# Qbot.net
KiCad netlist of a schematic drawn in Altium Designer
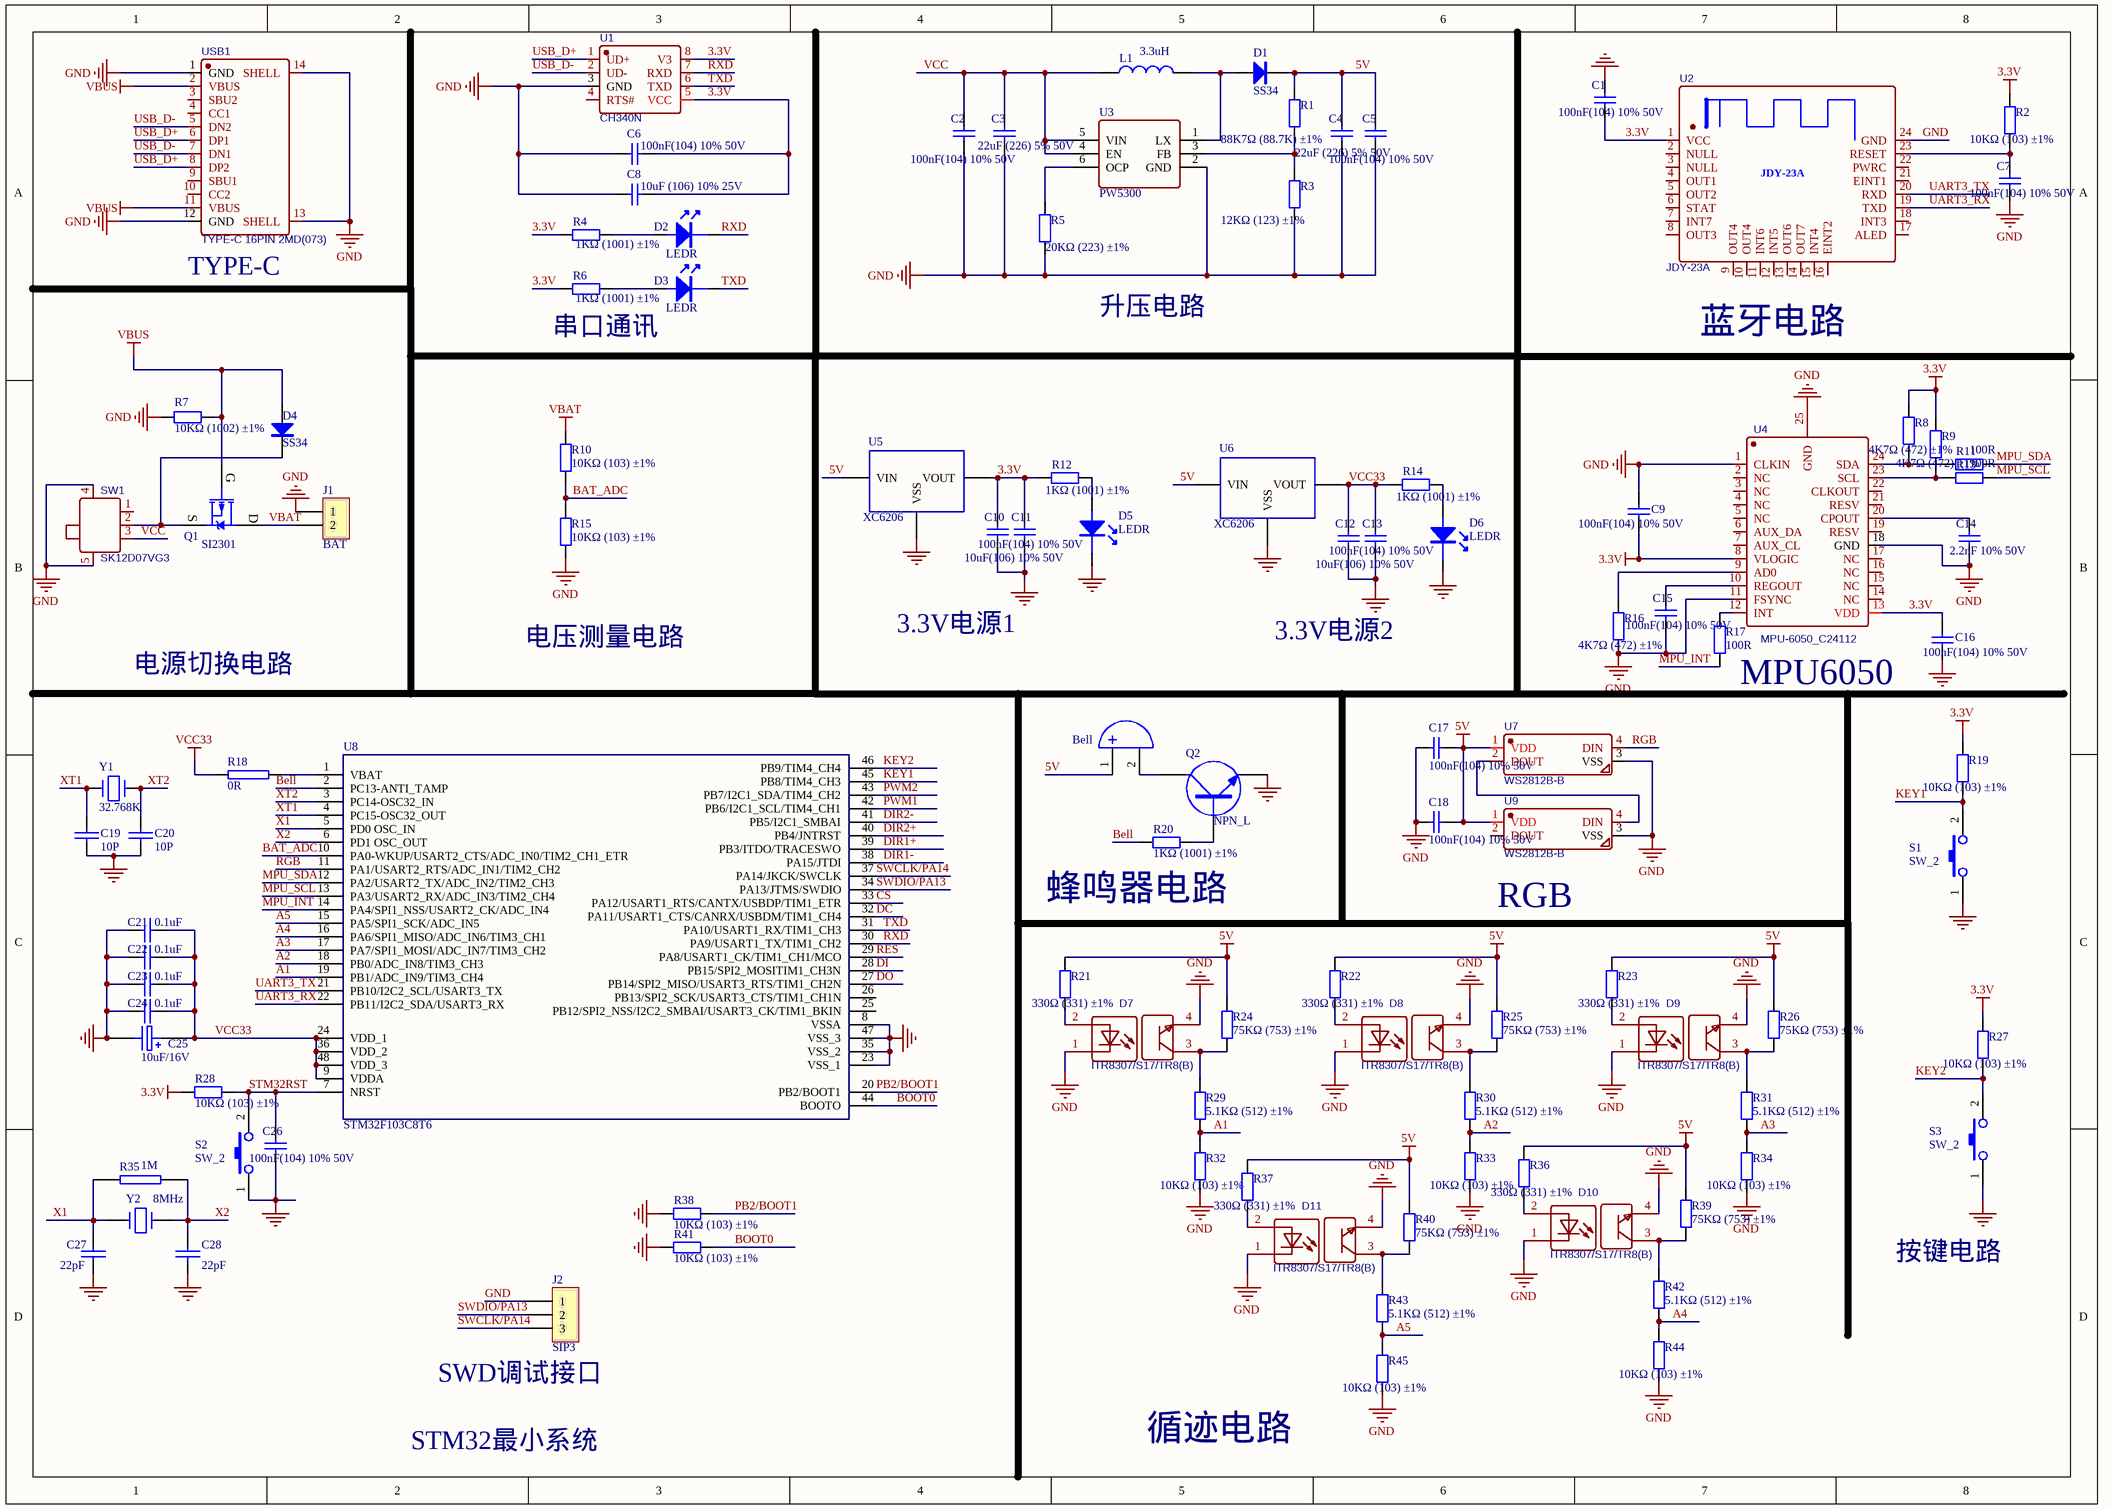
[diagram p0: Qbot.SchDoc]

(export (version "E")
  (design (tool "Eeschema 10.0.6"))
  (components
    (comp (ref "C1")
      (value "100nF(104) 10% 50V")
      (footprint "LC-0805_C")
      (description "贴片电容")
      (libsource (lib "Miscellaneous Devices LC") (part "0805 100nF(104) 10% 50V"))
    )
    (comp (ref "C2")
      (value "100nF(104) 10% 50V")
      (footprint "LC-0805_C")
      (description "贴片电容")
      (libsource (lib "Miscellaneous Devices LC") (part "0805 100nF(104) 10% 50V"))
    )
    (comp (ref "C3")
      (value "22uF (226) 5% 50V")
      (footprint "LC-0805_C")
      (description "贴片电容")
      (libsource (lib "Miscellaneous Devices LC") (part "0805 22pF (220) 5% 50V"))
    )
    (comp (ref "C4")
      (value "22uF (226) 5% 50V")
      (footprint "LC-0805_C")
      (description "贴片电容")
      (libsource (lib "Miscellaneous Devices LC") (part "0805 22pF (220) 5% 50V"))
    )
    (comp (ref "C5")
      (value "100nF(104) 10% 50V")
      (footprint "LC-0805_C")
      (description "贴片电容")
      (libsource (lib "Miscellaneous Devices LC") (part "0805 100nF(104) 10% 50V"))
    )
    (comp (ref "C6")
      (value "100nF(104) 10% 50V")
      (footprint "LC-0805_C")
      (description "贴片电容")
      (libsource (lib "Miscellaneous Devices LC") (part "0805 100nF(104) 10% 50V"))
    )
    (comp (ref "C7")
      (value "100nF(104) 10% 50V")
      (footprint "LC-0805_C")
      (description "贴片电容")
      (libsource (lib "Miscellaneous Devices LC") (part "0805 100nF(104) 10% 50V"))
    )
    (comp (ref "C8")
      (value "10uF (106) 10% 25V")
      (footprint "LC-0805_C")
      (description "贴片电容")
      (libsource (lib "Miscellaneous Devices LC") (part "0805 10uF (106) 10% 25V"))
    )
    (comp (ref "C9")
      (value "100nF(104) 10% 50V")
      (footprint "LC-0805_C")
      (description "贴片电容")
      (libsource (lib "Miscellaneous Devices LC") (part "0805 100nF(104) 10% 50V"))
    )
    (comp (ref "C10")
      (value "10uF(106) 10% 50V")
      (footprint "LC-0805_C")
      (description "贴片电容")
      (libsource (lib "Miscellaneous Devices LC") (part "0805 100nF(104) 10% 50V"))
    )
    (comp (ref "C11")
      (value "100nF(104) 10% 50V")
      (footprint "LC-0805_C")
      (description "贴片电容")
      (libsource (lib "Miscellaneous Devices LC") (part "0805 100nF(104) 10% 50V"))
    )
    (comp (ref "C12")
      (value "10uF(106) 10% 50V")
      (footprint "LC-0805_C")
      (description "贴片电容")
      (libsource (lib "Miscellaneous Devices LC") (part "0805 100nF(104) 10% 50V"))
    )
    (comp (ref "C13")
      (value "100nF(104) 10% 50V")
      (footprint "LC-0805_C")
      (description "贴片电容")
      (libsource (lib "Miscellaneous Devices LC") (part "0805 100nF(104) 10% 50V"))
    )
    (comp (ref "C14")
      (value "2.2nF 10% 50V")
      (footprint "LC-0805_C")
      (description "贴片电容")
      (libsource (lib "Miscellaneous Devices LC") (part "0805 100nF(104) 10% 50V"))
    )
    (comp (ref "C15")
      (value "100nF(104) 10% 50V")
      (footprint "LC-0805_C")
      (description "贴片电容")
      (libsource (lib "Miscellaneous Devices LC") (part "0805 100nF(104) 10% 50V"))
    )
    (comp (ref "C16")
      (value "100nF(104) 10% 50V")
      (footprint "LC-0805_C")
      (description "贴片电容")
      (libsource (lib "Miscellaneous Devices LC") (part "0805 100nF(104) 10% 50V"))
    )
    (comp (ref "C17")
      (value "100nF(104) 10% 50V")
      (footprint "LC-0805_C")
      (description "贴片电容")
      (libsource (lib "Miscellaneous Devices LC") (part "0805 100nF(104) 10% 50V"))
    )
    (comp (ref "C18")
      (value "100nF(104) 10% 50V")
      (footprint "LC-0805_C")
      (description "贴片电容")
      (libsource (lib "Miscellaneous Devices LC") (part "0805 100nF(104) 10% 50V"))
    )
    (comp (ref "C19") (value "10P") (footprint "LC-0805_C") (libsource (lib "*") (part "CAP")))
    (comp (ref "C20") (value "10P") (footprint "LC-0805_C") (libsource (lib "*") (part "CAP")))
    (comp (ref "C21")
      (value "0.1uF")
      (footprint "LC-0805_C")
      (description "Capacitor")
      (libsource (lib "") (part "CAP_1"))
    )
    (comp (ref "C22")
      (value "0.1uF")
      (footprint "LC-0805_C")
      (description "Capacitor")
      (libsource (lib "") (part "CAP_1"))
    )
    (comp (ref "C23")
      (value "0.1uF")
      (footprint "LC-0805_C")
      (description "Capacitor")
      (libsource (lib "") (part "CAP_1"))
    )
    (comp (ref "C24")
      (value "0.1uF")
      (footprint "LC-0805_C")
      (description "Capacitor")
      (libsource (lib "") (part "CAP_1"))
    )
    (comp (ref "C25")
      (value "10uF/16V")
      (footprint "LC-0805_C")
      (description "Electrolytic Capacitor")
      (libsource (lib "*") (part "ELECTRO1"))
    )
    (comp (ref "C26")
      (value "100nF(104) 10% 50V")
      (footprint "LC-0805_C")
      (description "贴片电容")
      (libsource (lib "Miscellaneous Devices LC") (part "0805 100nF(104) 10% 50V"))
    )
    (comp (ref "C27")
      (value "22pF")
      (footprint "LC-0805_C")
      (description "Capacitor")
      (libsource (lib "") (part "CAP_1"))
    )
    (comp (ref "C28")
      (value "22pF")
      (footprint "LC-0805_C")
      (description "Capacitor")
      (libsource (lib "") (part "CAP_1"))
    )
    (comp (ref "D1")
      (value "SS34")
      (footprint "SMA")
      (description "肖特基二极管")
      (fields (field (name "版权归属") "源创客"))
      (libsource (lib "8.1   - 二极管-整流桥") (part "SS34"))
    )
    (comp (ref "D2") (value "LEDR") (footprint "LED0805G") (libsource (lib "六路AD&六路DA_1") (part "LED")))
    (comp (ref "D3") (value "LEDR") (footprint "LED0805G") (libsource (lib "六路AD&六路DA_1") (part "LED")))
    (comp (ref "D4")
      (value "SS34")
      (footprint "SMA")
      (description "肖特基二极管")
      (fields (field (name "版权归属") "源创客"))
      (libsource (lib "8.1   - 二极管-整流桥") (part "SS34"))
    )
    (comp (ref "D5") (value "LEDR") (footprint "LED0805G") (libsource (lib "*") (part "LED")))
    (comp (ref "D6") (value "LEDR") (footprint "LED0805G") (libsource (lib "*") (part "LED")))
    (comp (ref "D7")
      (value "ITR8307/S17/TR8(B)")
      (footprint "OPTO-SMD_ITR8307-S17-TR8-B-BL")
      (fields (field (name "BOM_SUPPLIER PART") "C81632"))
      (libsource (lib "Qbot") (part "ITR8307/S17/TR8(B)"))
    )
    (comp (ref "D8")
      (value "ITR8307/S17/TR8(B)")
      (footprint "OPTO-SMD_ITR8307-S17-TR8-B-BL")
      (fields (field (name "BOM_SUPPLIER PART") "C81632"))
      (libsource (lib "Qbot") (part "ITR8307/S17/TR8(B)"))
    )
    (comp (ref "D9")
      (value "ITR8307/S17/TR8(B)")
      (footprint "OPTO-SMD_ITR8307-S17-TR8-B-BL")
      (fields (field (name "BOM_SUPPLIER PART") "C81632"))
      (libsource (lib "Qbot") (part "ITR8307/S17/TR8(B)"))
    )
    (comp (ref "D10")
      (value "ITR8307/S17/TR8(B)")
      (footprint "OPTO-SMD_ITR8307-S17-TR8-B-BL")
      (fields (field (name "BOM_SUPPLIER PART") "C81632"))
      (libsource (lib "Qbot") (part "ITR8307/S17/TR8(B)"))
    )
    (comp (ref "D11")
      (value "ITR8307/S17/TR8(B)")
      (footprint "OPTO-SMD_ITR8307-S17-TR8-B-BL")
      (fields (field (name "BOM_SUPPLIER PART") "C81632"))
      (libsource (lib "Qbot") (part "ITR8307/S17/TR8(B)"))
    )
    (comp (ref "J1")
      (value "BAT")
      (footprint "XH2.54-LI-2P")
      (description "jointbar")
      (libsource (lib "接口与插座") (part "SIP2"))
    )
    (comp (ref "J2")
      (value "SIP3")
      (footprint "HDR2.54-WI-3P")
      (description "jointbar")
      (libsource (lib "接口与插座") (part "SIP3"))
    )
    (comp (ref "L1")
      (value "3.3uH")
      (footprint "IND-SMD_L4.6-W4.1")
      (description "小功率贴片电感")
      (fields (field (name "版权归属") "源创客"))
      (libsource (lib "3.1   - 电阻-电容-电感") (part "L"))
    )
    (comp (ref "LS1")
      (value "Bell")
      (footprint "BELL")
      (description "Electrical Bell")
      (fields (field (name "PUBLISHER") "Altium Limited"))
      (libsource (lib "3DGeneral") (part "Bell"))
    )
    (comp (ref "Q1")
      (value "SI2301")
      (footprint "SOT23")
      (description "P沟道场效应管")
      (fields (field (name "版权归属") "源创客"))
      (libsource (lib "6.1   - 场效应管-可控硅") (part "SI2301"))
    )
    (comp (ref "Q2")
      (value "NPN_L")
      (footprint "SOT-23_S8050")
      (libsource (lib "Environment_Detector") (part "NPN_L"))
    )
    (comp (ref "R1")
      (value "88K7Ω (88.7K) ±1%")
      (footprint "LC-0805_R")
      (description "贴片电阻")
      (libsource (lib "Miscellaneous Devices LC") (part "0805 1KΩ (1001) 1%"))
    )
    (comp (ref "R2")
      (value "10KΩ (103) ±1%")
      (footprint "LC-0805_R")
      (description "贴片电阻")
      (libsource (lib "") (part "0805 1KΩ (1001) 1%_2"))
    )
    (comp (ref "R3")
      (value "12KΩ (123) ±1%")
      (footprint "LC-0805_R")
      (description "贴片电阻")
      (libsource (lib "Miscellaneous Devices LC") (part "0805 1KΩ (1001) 1%"))
    )
    (comp (ref "R4")
      (value "1KΩ (1001) ±1%")
      (footprint "LC-0805_R")
      (description "贴片电阻")
      (libsource (lib "") (part "0805 1KΩ (1001) 1%_1"))
    )
    (comp (ref "R5")
      (value "20KΩ (223) ±1%")
      (footprint "LC-0805_R")
      (description "贴片电阻")
      (libsource (lib "Miscellaneous Devices LC") (part "0805 1KΩ (1001) 1%"))
    )
    (comp (ref "R6")
      (value "1KΩ (1001) ±1%")
      (footprint "LC-0805_R")
      (description "贴片电阻")
      (libsource (lib "") (part "0805 1KΩ (1001) 1%_1"))
    )
    (comp (ref "R7")
      (value "10KΩ (1002) ±1%")
      (footprint "LC-0805_R")
      (description "贴片电阻")
      (libsource (lib "Miscellaneous Devices LC") (part "0805 10KΩ (1002) 1%"))
    )
    (comp (ref "R8")
      (value "4K7Ω (472) ±1%")
      (footprint "LC-0805_R")
      (description "贴片电阻")
      (libsource (lib "") (part "0805 1KΩ (1001) 1%_2"))
    )
    (comp (ref "R9")
      (value "4K7Ω (472) ±1%")
      (footprint "LC-0805_R")
      (description "贴片电阻")
      (libsource (lib "") (part "0805 1KΩ (1001) 1%_2"))
    )
    (comp (ref "R10")
      (value "10KΩ (103) ±1%")
      (footprint "LC-0805_R")
      (description "贴片电阻")
      (libsource (lib "") (part "0805 1KΩ (1001) 1%_2"))
    )
    (comp (ref "R11")
      (value "100R")
      (footprint "LC-0805_R")
      (description "贴片电阻")
      (libsource (lib "") (part "0805 1KΩ (1001) 1%_1"))
    )
    (comp (ref "R12")
      (value "1KΩ (1001) ±1%")
      (footprint "LC-0805_R")
      (description "贴片电阻")
      (libsource (lib "") (part "0805 1KΩ (1001) 1%_1"))
    )
    (comp (ref "R13")
      (value "100R")
      (footprint "LC-0805_R")
      (description "贴片电阻")
      (libsource (lib "") (part "0805 1KΩ (1001) 1%_1"))
    )
    (comp (ref "R14")
      (value "1KΩ (1001) ±1%")
      (footprint "LC-0805_R")
      (description "贴片电阻")
      (libsource (lib "") (part "0805 1KΩ (1001) 1%_1"))
    )
    (comp (ref "R15")
      (value "10KΩ (103) ±1%")
      (footprint "LC-0805_R")
      (description "贴片电阻")
      (libsource (lib "") (part "0805 1KΩ (1001) 1%_2"))
    )
    (comp (ref "R16")
      (value "4K7Ω (472) ±1%")
      (footprint "LC-0805_R")
      (description "贴片电阻")
      (libsource (lib "") (part "0805 1KΩ (1001) 1%_2"))
    )
    (comp (ref "R17")
      (value "100R")
      (footprint "LC-0805_R")
      (description "贴片电阻")
      (libsource (lib "Miscellaneous Devices LC") (part "0805 1KΩ (1001) 1%"))
    )
    (comp (ref "R18") (value "0R") (footprint "LC-0805_R") (libsource (lib "*") (part "RES")))
    (comp (ref "R19")
      (value "10KΩ (103) ±1%")
      (footprint "LC-0805_R")
      (description "贴片电阻")
      (libsource (lib "") (part "0805 1KΩ (1001) 1%_2"))
    )
    (comp (ref "R20")
      (value "1KΩ (1001) ±1%")
      (footprint "LC-0805_R")
      (description "贴片电阻")
      (libsource (lib "") (part "0805 1KΩ (1001) 1%_1"))
    )
    (comp (ref "R21")
      (value "330Ω (331) ±1%")
      (footprint "LC-0805_R")
      (description "贴片电阻")
      (libsource (lib "Miscellaneous Devices LC") (part "0805 1KΩ (1001) 1%"))
    )
    (comp (ref "R22")
      (value "330Ω (331) ±1%")
      (footprint "LC-0805_R")
      (description "贴片电阻")
      (libsource (lib "Miscellaneous Devices LC") (part "0805 1KΩ (1001) 1%"))
    )
    (comp (ref "R23")
      (value "330Ω (331) ±1%")
      (footprint "LC-0805_R")
      (description "贴片电阻")
      (libsource (lib "Miscellaneous Devices LC") (part "0805 1KΩ (1001) 1%"))
    )
    (comp (ref "R24")
      (value "75KΩ (753) ±1%")
      (footprint "LC-0805_R")
      (description "贴片电阻")
      (libsource (lib "") (part "0805 1KΩ (1001) 1%_2"))
    )
    (comp (ref "R25")
      (value "75KΩ (753) ±1%")
      (footprint "LC-0805_R")
      (description "贴片电阻")
      (libsource (lib "") (part "0805 1KΩ (1001) 1%_2"))
    )
    (comp (ref "R26")
      (value "75KΩ (753) ±1%")
      (footprint "LC-0805_R")
      (description "贴片电阻")
      (libsource (lib "") (part "0805 1KΩ (1001) 1%_2"))
    )
    (comp (ref "R27")
      (value "10KΩ (103) ±1%")
      (footprint "LC-0805_R")
      (description "贴片电阻")
      (libsource (lib "") (part "0805 1KΩ (1001) 1%_2"))
    )
    (comp (ref "R28")
      (value "10KΩ (103) ±1%")
      (footprint "LC-0805_R")
      (description "贴片电阻")
      (libsource (lib "") (part "0805 1KΩ (1001) 1%_3"))
    )
    (comp (ref "R29")
      (value "5.1KΩ (512) ±1%")
      (footprint "LC-0805_R")
      (description "贴片电阻")
      (libsource (lib "Miscellaneous Devices LC") (part "0805 1KΩ (1001) 1%"))
    )
    (comp (ref "R30")
      (value "5.1KΩ (512) ±1%")
      (footprint "LC-0805_R")
      (description "贴片电阻")
      (libsource (lib "Miscellaneous Devices LC") (part "0805 1KΩ (1001) 1%"))
    )
    (comp (ref "R31")
      (value "5.1KΩ (512) ±1%")
      (footprint "LC-0805_R")
      (description "贴片电阻")
      (libsource (lib "Miscellaneous Devices LC") (part "0805 1KΩ (1001) 1%"))
    )
    (comp (ref "R32")
      (value "10KΩ (103) ±1%")
      (footprint "LC-0805_R")
      (description "贴片电阻")
      (libsource (lib "") (part "0805 1KΩ (1001) 1%_2"))
    )
    (comp (ref "R33")
      (value "10KΩ (103) ±1%")
      (footprint "LC-0805_R")
      (description "贴片电阻")
      (libsource (lib "") (part "0805 1KΩ (1001) 1%_2"))
    )
    (comp (ref "R34")
      (value "10KΩ (103) ±1%")
      (footprint "LC-0805_R")
      (description "贴片电阻")
      (libsource (lib "") (part "0805 1KΩ (1001) 1%_2"))
    )
    (comp (ref "R35") (value "1M") (footprint "LC-0805_R") (libsource (lib "*") (part "RES2")))
    (comp (ref "R36")
      (value "330Ω (331) ±1%")
      (footprint "LC-0805_R")
      (description "贴片电阻")
      (libsource (lib "Miscellaneous Devices LC") (part "0805 1KΩ (1001) 1%"))
    )
    (comp (ref "R37")
      (value "330Ω (331) ±1%")
      (footprint "LC-0805_R")
      (description "贴片电阻")
      (libsource (lib "Miscellaneous Devices LC") (part "0805 1KΩ (1001) 1%"))
    )
    (comp (ref "R38")
      (value "10KΩ (103) ±1%")
      (footprint "LC-0805_R")
      (description "贴片电阻")
      (libsource (lib "") (part "0805 1KΩ (1001) 1%_1"))
    )
    (comp (ref "R39")
      (value "75KΩ (753) ±1%")
      (footprint "LC-0805_R")
      (description "贴片电阻")
      (libsource (lib "") (part "0805 1KΩ (1001) 1%_2"))
    )
    (comp (ref "R40")
      (value "75KΩ (753) ±1%")
      (footprint "LC-0805_R")
      (description "贴片电阻")
      (libsource (lib "") (part "0805 1KΩ (1001) 1%_2"))
    )
    (comp (ref "R41")
      (value "10KΩ (103) ±1%")
      (footprint "LC-0805_R")
      (description "贴片电阻")
      (libsource (lib "") (part "0805 1KΩ (1001) 1%_1"))
    )
    (comp (ref "R42")
      (value "5.1KΩ (512) ±1%")
      (footprint "LC-0805_R")
      (description "贴片电阻")
      (libsource (lib "Miscellaneous Devices LC") (part "0805 1KΩ (1001) 1%"))
    )
    (comp (ref "R43")
      (value "5.1KΩ (512) ±1%")
      (footprint "LC-0805_R")
      (description "贴片电阻")
      (libsource (lib "Miscellaneous Devices LC") (part "0805 1KΩ (1001) 1%"))
    )
    (comp (ref "R44")
      (value "10KΩ (103) ±1%")
      (footprint "LC-0805_R")
      (description "贴片电阻")
      (libsource (lib "") (part "0805 1KΩ (1001) 1%_2"))
    )
    (comp (ref "R45")
      (value "10KΩ (103) ±1%")
      (footprint "LC-0805_R")
      (description "贴片电阻")
      (libsource (lib "") (part "0805 1KΩ (1001) 1%_2"))
    )
    (comp (ref "S1") (value "SW_2") (footprint "TSW SMD-3*6*2.5") (libsource (lib "*") (part "SW_2")))
    (comp (ref "S2") (value "SW_2") (footprint "TSW SMD-3*6*2.5") (libsource (lib "*") (part "SW_2")))
    (comp (ref "S3") (value "SW_2") (footprint "TSW SMD-3*6*2.5") (libsource (lib "*") (part "SW_2")))
    (comp (ref "SW1")
      (value "SK12D07VG3")
      (footprint "SW-TH_SK-12D07-VG3")
      (fields
        (field (name "BOM_SUPPLIER PART") "C2681575")
        (field (name "BOM_MANUFACTURER PART") "SK12D07VG6")
        (field (name "CONTRIBUTOR") "LCSC")
      )
      (libsource (lib "Qbot") (part "SK12D07VG6"))
    )
    (comp (ref "U1")
      (value "CH340N")
      (footprint "SOP8")
      (fields
        (field (name "BOM_SUPPLIER PART") "C506813")
        (field (name "SUBPART_NO") "1")
        (field (name "CONTRIBUTOR") "LCSC")
      )
      (libsource (lib "Qbot") (part "CH340N"))
    )
    (comp (ref "U2")
      (value "JDY-23A")
      (footprint "JDY-23A")
      (fields
        (field (name "BOM_MANUFACTURER PART") "HY-40R204P")
        (field (name "BOM_SUPPLIER PART") "C172803")
        (field (name "CONTRIBUTOR") "LCSC")
      )
      (libsource (lib "Qbot") (part "JDY-23A"))
    )
    (comp (ref "U3") (value "PW5300") (footprint "SOT23-6L") (libsource (lib "Qbot") (part "PW5300")))
    (comp (ref "U4")
      (value "MPU-6050_C24112")
      (footprint "QFN24")
      (fields (field (name "BOM_MANUFACTURER PART") "MPU-6050") (field (name "BOM_SUPPLIER PART") "C24112"))
      (libsource (lib "Qbot") (part "MPU-6050_C24112"))
    )
    (comp (ref "U5") (value "XC6206") (footprint "SOT-23_TL431") (libsource (lib "*") (part "XC6206")))
    (comp (ref "U6") (value "XC6206") (footprint "SOT-23_TL431") (libsource (lib "*") (part "XC6206")))
    (comp (ref "U7")
      (value "WS2812B-B")
      (footprint "LED-SMD_4P-L5.0-W5.0-TL_WS2812B-B")
      (fields (field (name "BOM_SUPPLIER PART") "C114586") (field (name "CONTRIBUTOR") "LCSC"))
      (libsource (lib "Qbot") (part "WS2812B-B"))
    )
    (comp (ref "U8")
      (value "STM32F103C8T6")
      (footprint "STM32F103C8T6_LQFP48")
      (libsource (lib "*") (part "STM32F103C8T6"))
    )
    (comp (ref "U9")
      (value "WS2812B-B")
      (footprint "LED-SMD_4P-L5.0-W5.0-TL_WS2812B-B")
      (fields (field (name "BOM_SUPPLIER PART") "C114586") (field (name "CONTRIBUTOR") "LCSC"))
      (libsource (lib "Qbot") (part "WS2812B-B"))
    )
    (comp (ref "USB1")
      (value "TYPE-C 16PIN 2MD(073)")
      (footprint "USB-C-SMD_TYPE-C-6PIN-2MD-073")
      (fields (field (name "BOM_SUPPLIER PART") "C2765186") (field (name "CONTRIBUTOR") "LCSC"))
      (libsource (lib "Qbot") (part "TYPE-C 16PIN 2MD(073)"))
    )
    (comp (ref "Y1")
      (value "32.768K")
      (footprint "OSC-3x10-WI-A")
      (description "晶振")
      (libsource (lib "*") (part "CRYSTAL"))
    )
    (comp (ref "Y2")
      (value "8MHz")
      (footprint "OSC HC-49S")
      (description "Crystal")
      (libsource (lib "*") (part "XTAL"))
    )
  )
  (nets
    (net (code "1") (name "/A1") (class "Default")
      (node (ref "R29") (pin "1") (pinfunction "1_1") (pintype "passive"))
      (node (ref "R32") (pin "1") (pinfunction "1_1") (pintype "passive"))
      (node (ref "U8") (pin "19") (pinfunction "PB1/ADC_IN9/TIM3_CH4_19") (pintype "passive"))
    )
    (net (code "2") (name "/A2") (class "Default")
      (node (ref "R30") (pin "1") (pinfunction "1_1") (pintype "passive"))
      (node (ref "R33") (pin "1") (pinfunction "1_1") (pintype "passive"))
      (node (ref "U8") (pin "18") (pinfunction "PB0/ADC_IN8/TIM3_CH3_18") (pintype "passive"))
    )
    (net (code "3") (name "/A3") (class "Default")
      (node (ref "R31") (pin "1") (pinfunction "1_1") (pintype "passive"))
      (node (ref "R34") (pin "1") (pinfunction "1_1") (pintype "passive"))
      (node (ref "U8") (pin "17") (pinfunction "PA7/SPI1_MOSI/ADC_IN7/TIM3_CH2_17") (pintype "passive"))
    )
    (net (code "4") (name "/A4") (class "Default")
      (node (ref "R42") (pin "1") (pinfunction "1_1") (pintype "passive"))
      (node (ref "R44") (pin "1") (pinfunction "1_1") (pintype "passive"))
      (node (ref "U8") (pin "16") (pinfunction "PA6/SPI1_MISO/ADC_IN6/TIM3_CH1_16") (pintype "passive"))
    )
    (net (code "5") (name "/A5") (class "Default")
      (node (ref "R43") (pin "1") (pinfunction "1_1") (pintype "passive"))
      (node (ref "R45") (pin "1") (pinfunction "1_1") (pintype "passive"))
      (node (ref "U8") (pin "15") (pinfunction "PA5/SPI1_SCK/ADC_IN5_15") (pintype "passive"))
    )
    (net (code "6") (name "/BAT_ADC") (class "Default")
      (node (ref "R10") (pin "2") (pinfunction "2_2") (pintype "passive"))
      (node (ref "R15") (pin "1") (pinfunction "1_1") (pintype "passive"))
      (node (ref "U8") (pin "10") (pinfunction "PA0-WKUP/USART2_CTS/ADC_IN0/TIM2_CH1_ETR_10") (pintype "passive"))
    )
    (net (code "7") (name "/BOOT0") (class "Default")
      (node (ref "R41") (pin "2") (pinfunction "2_2") (pintype "passive"))
      (node (ref "U8") (pin "44") (pinfunction "BOOTO_44") (pintype "passive"))
    )
    (net (code "8") (name "/Bell") (class "Default")
      (node (ref "R20") (pin "1") (pinfunction "1_1") (pintype "passive"))
      (node (ref "U8") (pin "2") (pinfunction "PC13-ANTI_TAMP_2") (pintype "passive"))
    )
    (net (code "9") (name "/CS") (class "Default")
      (node (ref "U8") (pin "33") (pinfunction "PA12/USART1_RTS/CANTX/USBDP/TIM1_ETR_33") (pintype "passive"))
    )
    (net (code "10") (name "/DC") (class "Default")
      (node (ref "U8") (pin "32") (pinfunction "PA11/USART1_CTS/CANRX/USBDM/TIM1_CH4_32") (pintype "passive"))
    )
    (net (code "11") (name "/DI") (class "Default")
      (node (ref "U8") (pin "28") (pinfunction "PB15/SPI2_MOSITIM1_CH3N_28") (pintype "passive"))
    )
    (net (code "12") (name "/DIR1+") (class "Default")
      (node (ref "U8") (pin "39") (pinfunction "PB3/ITDO/TRACESWO_39") (pintype "passive"))
    )
    (net (code "13") (name "/DIR1-") (class "Default")
      (node (ref "U8") (pin "38") (pinfunction "PA15/JTDI_38") (pintype "passive"))
    )
    (net (code "14") (name "/DIR2+") (class "Default")
      (node (ref "U8") (pin "40") (pinfunction "PB4/JNTRST_40") (pintype "passive"))
    )
    (net (code "15") (name "/DIR2-") (class "Default")
      (node (ref "U8") (pin "41") (pinfunction "PB5/I2C1_SMBAI_41") (pintype "passive"))
    )
    (net (code "16") (name "/DO") (class "Default")
      (node (ref "U8") (pin "27") (pinfunction "PB14/SPI2_MISO/USART3_RTS/TIM1_CH2N_27") (pintype "passive"))
    )
    (net (code "17") (name "/KEY1") (class "Default")
      (node (ref "R19") (pin "2") (pinfunction "2_2") (pintype "passive"))
      (node (ref "S1") (pin "2") (pintype "passive"))
      (node (ref "U8") (pin "45") (pinfunction "PB8/TIM4_CH3_45") (pintype "passive"))
    )
    (net (code "18") (name "/KEY2") (class "Default")
      (node (ref "R27") (pin "2") (pinfunction "2_2") (pintype "passive"))
      (node (ref "S3") (pin "2") (pintype "passive"))
      (node (ref "U8") (pin "46") (pinfunction "PB9/TIM4_CH4_46") (pintype "passive"))
    )
    (net (code "19") (name "/MPU_INT") (class "Default")
      (node (ref "R17") (pin "1") (pinfunction "1_1") (pintype "passive"))
      (node (ref "U8") (pin "14") (pinfunction "PA4/SPI1_NSS/USART2_CK/ADC_IN4_14") (pintype "passive"))
    )
    (net (code "20") (name "/MPU_SCL") (class "Default")
      (node (ref "R13") (pin "2") (pinfunction "2_2") (pintype "passive"))
      (node (ref "U8") (pin "13") (pinfunction "PA3/USART2_RX/ADC_IN3/TIM2_CH4_13") (pintype "passive"))
    )
    (net (code "21") (name "/MPU_SDA") (class "Default")
      (node (ref "R11") (pin "2") (pinfunction "2_2") (pintype "passive"))
      (node (ref "U8") (pin "12") (pinfunction "PA2/USART2_TX/ADC_IN2/TIM2_CH3_12") (pintype "passive"))
    )
    (net (code "22") (name "/PB2{slash}BOOT1") (class "Default")
      (node (ref "R38") (pin "2") (pinfunction "2_2") (pintype "passive"))
      (node (ref "U8") (pin "20") (pinfunction "PB2/BOOT1_20") (pintype "passive"))
    )
    (net (code "23") (name "/PWM1") (class "Default")
      (node (ref "U8") (pin "42") (pinfunction "PB6/I2C1_SCL/TIM4_CH1_42") (pintype "passive"))
    )
    (net (code "24") (name "/PWM2") (class "Default")
      (node (ref "U8") (pin "43") (pinfunction "PB7/I2C1_SDA/TIM4_CH2_43") (pintype "passive"))
    )
    (net (code "25") (name "/RES") (class "Default")
      (node (ref "U8") (pin "29") (pinfunction "PA8/USART1_CK/TIM1_CH1/MCO_29") (pintype "passive"))
    )
    (net (code "26") (name "/RGB") (class "Default")
      (node (ref "U7") (pin "4") (pinfunction "DIN_4") (pintype "passive"))
      (node (ref "U8") (pin "11") (pinfunction "PA1/USART2_RTS/ADC_IN1/TIM2_CH2_11") (pintype "passive"))
    )
    (net (code "27") (name "/RXD") (class "Default")
      (node (ref "D2") (pin "2") (pintype "passive"))
      (node (ref "U1") (pin "7") (pinfunction "RXD_7") (pintype "passive"))
      (node (ref "U8") (pin "30") (pinfunction "PA9/USART1_TX/TIM1_CH2_30") (pintype "passive"))
    )
    (net (code "28") (name "/STM32RST") (class "Default")
      (node (ref "C26") (pin "1") (pinfunction "1_1") (pintype "passive"))
      (node (ref "R28") (pin "1") (pinfunction "1_1") (pintype "passive"))
      (node (ref "S2") (pin "2") (pintype "passive"))
      (node (ref "U8") (pin "7") (pinfunction "NRST_7") (pintype "passive"))
    )
    (net (code "29") (name "/SWCLK{slash}PA14") (class "Default")
      (node (ref "J2") (pin "3") (pinfunction "3_3") (pintype "passive"))
      (node (ref "U8") (pin "37") (pinfunction "PA14/JKCK/SWCLK_37") (pintype "passive"))
    )
    (net (code "30") (name "/SWDIO{slash}PA13") (class "Default")
      (node (ref "J2") (pin "2") (pinfunction "2_2") (pintype "passive"))
      (node (ref "U8") (pin "34") (pinfunction "PA13/JTMS/SWDIO_34") (pintype "passive"))
    )
    (net (code "31") (name "/TXD") (class "Default")
      (node (ref "D3") (pin "2") (pintype "passive"))
      (node (ref "U1") (pin "6") (pinfunction "TXD_6") (pintype "passive"))
      (node (ref "U8") (pin "31") (pinfunction "PA10/USART1_RX/TIM1_CH3_31") (pintype "passive"))
    )
    (net (code "32") (name "/UART3_RX") (class "Default")
      (node (ref "U2") (pin "19") (pinfunction "TXD_19") (pintype "passive"))
      (node (ref "U8") (pin "22") (pinfunction "PB11/I2C2_SDA/USART3_RX_22") (pintype "passive"))
    )
    (net (code "33") (name "/UART3_TX") (class "Default")
      (node (ref "U2") (pin "20") (pinfunction "RXD_20") (pintype "passive"))
      (node (ref "U8") (pin "21") (pinfunction "PB10/I2C2_SCL/USART3_TX_21") (pintype "passive"))
    )
    (net (code "34") (name "/USB_D+") (class "Default")
      (node (ref "U1") (pin "1") (pinfunction "UD+_1") (pintype "passive"))
      (node (ref "USB1") (pin "6") (pinfunction "DP1_6") (pintype "passive"))
      (node (ref "USB1") (pin "8") (pinfunction "DP2_8") (pintype "passive"))
    )
    (net (code "35") (name "/USB_D-") (class "Default")
      (node (ref "U1") (pin "2") (pinfunction "UD-_2") (pintype "passive"))
      (node (ref "USB1") (pin "5") (pinfunction "DN2_5") (pintype "passive"))
      (node (ref "USB1") (pin "7") (pinfunction "DN1_7") (pintype "passive"))
    )
    (net (code "36") (name "/VCC") (class "Default")
      (node (ref "C2") (pin "1") (pinfunction "1_1") (pintype "passive"))
      (node (ref "C3") (pin "2") (pinfunction "2_2") (pintype "passive"))
      (node (ref "L1") (pin "1") (pinfunction "1_1") (pintype "passive"))
      (node (ref "SW1") (pin "3") (pinfunction "3_3") (pintype "passive"))
      (node (ref "U3") (pin "4") (pinfunction "EN_4") (pintype "passive"))
      (node (ref "U3") (pin "5") (pinfunction "VIN_5") (pintype "passive"))
    )
    (net (code "37") (name "/X1") (class "Default")
      (node (ref "C27") (pin "1") (pinfunction "1_1") (pintype "passive"))
      (node (ref "R35") (pin "1") (pinfunction "1_1") (pintype "passive"))
      (node (ref "U8") (pin "5") (pinfunction "PD0_OSC_IN_5") (pintype "passive"))
      (node (ref "Y2") (pin "1") (pinfunction "1_1") (pintype "passive"))
    )
    (net (code "38") (name "/X2") (class "Default")
      (node (ref "C28") (pin "1") (pinfunction "1_1") (pintype "passive"))
      (node (ref "R35") (pin "2") (pinfunction "2_2") (pintype "passive"))
      (node (ref "U8") (pin "6") (pinfunction "PD1_OSC_OUT_6") (pintype "passive"))
      (node (ref "Y2") (pin "2") (pinfunction "2_2") (pintype "passive"))
    )
    (net (code "39") (name "/XT1") (class "Default")
      (node (ref "C19") (pin "2") (pintype "passive"))
      (node (ref "U8") (pin "4") (pinfunction "PC15-OSC32_OUT_4") (pintype "passive"))
      (node (ref "Y1") (pin "2") (pintype "passive"))
    )
    (net (code "40") (name "/XT2") (class "Default")
      (node (ref "C20") (pin "2") (pintype "passive"))
      (node (ref "U8") (pin "3") (pinfunction "PC14-OSC32_IN_3") (pintype "passive"))
      (node (ref "Y1") (pin "1") (pintype "passive"))
    )
    (net (code "41") (name "3.3V") (class "Default")
      (node (ref "C1") (pin "2") (pinfunction "2_2") (pintype "passive"))
      (node (ref "C10") (pin "1") (pinfunction "1_1") (pintype "passive"))
      (node (ref "C11") (pin "1") (pinfunction "1_1") (pintype "passive"))
      (node (ref "C16") (pin "2") (pinfunction "2_2") (pintype "passive"))
      (node (ref "C6") (pin "1") (pinfunction "1_1") (pintype "passive"))
      (node (ref "C8") (pin "1") (pinfunction "1_1") (pintype "passive"))
      (node (ref "C9") (pin "1") (pinfunction "1_1") (pintype "passive"))
      (node (ref "R12") (pin "1") (pinfunction "1_1") (pintype "passive"))
      (node (ref "R19") (pin "1") (pinfunction "1_1") (pintype "passive"))
      (node (ref "R2") (pin "1") (pinfunction "1_1") (pintype "passive"))
      (node (ref "R27") (pin "1") (pinfunction "1_1") (pintype "passive"))
      (node (ref "R28") (pin "2") (pinfunction "2_2") (pintype "passive"))
      (node (ref "R4") (pin "1") (pinfunction "1_1") (pintype "passive"))
      (node (ref "R6") (pin "1") (pinfunction "1_1") (pintype "passive"))
      (node (ref "R8") (pin "1") (pinfunction "1_1") (pintype "passive"))
      (node (ref "R9") (pin "1") (pinfunction "1_1") (pintype "passive"))
      (node (ref "U1") (pin "5") (pinfunction "VCC_5") (pintype "passive"))
      (node (ref "U1") (pin "8") (pinfunction "V3_8") (pintype "passive"))
      (node (ref "U2") (pin "1") (pinfunction "VCC_1") (pintype "passive"))
      (node (ref "U4") (pin "13") (pinfunction "VDD_13") (pintype "passive"))
      (node (ref "U4") (pin "8") (pinfunction "VLOGIC_8") (pintype "passive"))
      (node (ref "U5") (pin "2") (pinfunction "VOUT_2") (pintype "passive"))
    )
    (net (code "42") (name "5V") (class "Default")
      (node (ref "C17") (pin "1") (pinfunction "1_1") (pintype "passive"))
      (node (ref "C18") (pin "1") (pinfunction "1_1") (pintype "passive"))
      (node (ref "C4") (pin "2") (pinfunction "2_2") (pintype "passive"))
      (node (ref "C5") (pin "1") (pinfunction "1_1") (pintype "passive"))
      (node (ref "D1") (pin "2") (pinfunction "K_2") (pintype "passive"))
      (node (ref "LS1") (pin "1") (pinfunction "A_1") (pintype "passive"))
      (node (ref "R1") (pin "2") (pinfunction "2_2") (pintype "passive"))
      (node (ref "R21") (pin "2") (pinfunction "2_2") (pintype "passive"))
      (node (ref "R22") (pin "2") (pinfunction "2_2") (pintype "passive"))
      (node (ref "R23") (pin "2") (pinfunction "2_2") (pintype "passive"))
      (node (ref "R24") (pin "1") (pinfunction "1_1") (pintype "passive"))
      (node (ref "R25") (pin "1") (pinfunction "1_1") (pintype "passive"))
      (node (ref "R26") (pin "1") (pinfunction "1_1") (pintype "passive"))
      (node (ref "R36") (pin "2") (pinfunction "2_2") (pintype "passive"))
      (node (ref "R37") (pin "2") (pinfunction "2_2") (pintype "passive"))
      (node (ref "R39") (pin "1") (pinfunction "1_1") (pintype "passive"))
      (node (ref "R40") (pin "1") (pinfunction "1_1") (pintype "passive"))
      (node (ref "U5") (pin "3") (pinfunction "VIN_3") (pintype "passive"))
      (node (ref "U6") (pin "3") (pinfunction "VIN_3") (pintype "passive"))
      (node (ref "U7") (pin "1") (pinfunction "VDD_1") (pintype "passive"))
      (node (ref "U9") (pin "1") (pinfunction "VDD_1") (pintype "passive"))
    )
    (net (code "43") (name "GND") (class "Default")
      (node (ref "C1") (pin "1") (pinfunction "1_1") (pintype "passive"))
      (node (ref "C10") (pin "2") (pinfunction "2_2") (pintype "passive"))
      (node (ref "C11") (pin "2") (pinfunction "2_2") (pintype "passive"))
      (node (ref "C12") (pin "2") (pinfunction "2_2") (pintype "passive"))
      (node (ref "C13") (pin "2") (pinfunction "2_2") (pintype "passive"))
      (node (ref "C14") (pin "2") (pinfunction "2_2") (pintype "passive"))
      (node (ref "C15") (pin "2") (pinfunction "2_2") (pintype "passive"))
      (node (ref "C16") (pin "1") (pinfunction "1_1") (pintype "passive"))
      (node (ref "C17") (pin "2") (pinfunction "2_2") (pintype "passive"))
      (node (ref "C18") (pin "2") (pinfunction "2_2") (pintype "passive"))
      (node (ref "C19") (pin "1") (pintype "passive"))
      (node (ref "C2") (pin "2") (pinfunction "2_2") (pintype "passive"))
      (node (ref "C20") (pin "1") (pintype "passive"))
      (node (ref "C21") (pin "2") (pinfunction "2_2") (pintype "passive"))
      (node (ref "C22") (pin "2") (pinfunction "2_2") (pintype "passive"))
      (node (ref "C23") (pin "2") (pinfunction "2_2") (pintype "passive"))
      (node (ref "C24") (pin "2") (pinfunction "2_2") (pintype "passive"))
      (node (ref "C25") (pin "2") (pinfunction "2_2") (pintype "passive"))
      (node (ref "C26") (pin "2") (pinfunction "2_2") (pintype "passive"))
      (node (ref "C27") (pin "2") (pinfunction "2_2") (pintype "passive"))
      (node (ref "C28") (pin "2") (pinfunction "2_2") (pintype "passive"))
      (node (ref "C3") (pin "1") (pinfunction "1_1") (pintype "passive"))
      (node (ref "C4") (pin "1") (pinfunction "1_1") (pintype "passive"))
      (node (ref "C5") (pin "2") (pinfunction "2_2") (pintype "passive"))
      (node (ref "C6") (pin "2") (pinfunction "2_2") (pintype "passive"))
      (node (ref "C7") (pin "2") (pinfunction "2_2") (pintype "passive"))
      (node (ref "C8") (pin "2") (pinfunction "2_2") (pintype "passive"))
      (node (ref "C9") (pin "2") (pinfunction "2_2") (pintype "passive"))
      (node (ref "D10") (pin "1") (pinfunction "1_1") (pintype "passive"))
      (node (ref "D10") (pin "4") (pinfunction "4_4") (pintype "passive"))
      (node (ref "D11") (pin "1") (pinfunction "1_1") (pintype "passive"))
      (node (ref "D11") (pin "4") (pinfunction "4_4") (pintype "passive"))
      (node (ref "D5") (pin "2") (pintype "passive"))
      (node (ref "D6") (pin "2") (pintype "passive"))
      (node (ref "D7") (pin "1") (pinfunction "1_1") (pintype "passive"))
      (node (ref "D7") (pin "4") (pinfunction "4_4") (pintype "passive"))
      (node (ref "D8") (pin "1") (pinfunction "1_1") (pintype "passive"))
      (node (ref "D8") (pin "4") (pinfunction "4_4") (pintype "passive"))
      (node (ref "D9") (pin "1") (pinfunction "1_1") (pintype "passive"))
      (node (ref "D9") (pin "4") (pinfunction "4_4") (pintype "passive"))
      (node (ref "J1") (pin "1") (pinfunction "1_1") (pintype "passive"))
      (node (ref "J2") (pin "1") (pinfunction "1_1") (pintype "passive"))
      (node (ref "Q2") (pin "2") (pinfunction "E_2") (pintype "passive"))
      (node (ref "R15") (pin "2") (pinfunction "2_2") (pintype "passive"))
      (node (ref "R16") (pin "2") (pinfunction "2_2") (pintype "passive"))
      (node (ref "R3") (pin "1") (pinfunction "1_1") (pintype "passive"))
      (node (ref "R32") (pin "2") (pinfunction "2_2") (pintype "passive"))
      (node (ref "R33") (pin "2") (pinfunction "2_2") (pintype "passive"))
      (node (ref "R34") (pin "2") (pinfunction "2_2") (pintype "passive"))
      (node (ref "R38") (pin "1") (pinfunction "1_1") (pintype "passive"))
      (node (ref "R41") (pin "1") (pinfunction "1_1") (pintype "passive"))
      (node (ref "R44") (pin "2") (pinfunction "2_2") (pintype "passive"))
      (node (ref "R45") (pin "2") (pinfunction "2_2") (pintype "passive"))
      (node (ref "R5") (pin "1") (pinfunction "1_1") (pintype "passive"))
      (node (ref "R7") (pin "1") (pinfunction "1_1") (pintype "passive"))
      (node (ref "S1") (pin "1") (pintype "passive"))
      (node (ref "S2") (pin "1") (pintype "passive"))
      (node (ref "S3") (pin "1") (pintype "passive"))
      (node (ref "SW1") (pin "4") (pinfunction "4_4") (pintype "passive"))
      (node (ref "SW1") (pin "5") (pinfunction "5_5") (pintype "passive"))
      (node (ref "U1") (pin "3") (pinfunction "GND_3") (pintype "passive"))
      (node (ref "U2") (pin "24") (pinfunction "GND_24") (pintype "passive"))
      (node (ref "U3") (pin "2") (pinfunction "GND_2") (pintype "passive"))
      (node (ref "U4") (pin "1") (pinfunction "CLKIN_1") (pintype "passive"))
      (node (ref "U4") (pin "11") (pinfunction "FSYNC_11") (pintype "passive"))
      (node (ref "U4") (pin "18") (pinfunction "GND_18") (pintype "passive"))
      (node (ref "U4") (pin "25") (pinfunction "GND_25") (pintype "passive"))
      (node (ref "U5") (pin "1") (pinfunction "VSS_1") (pintype "passive"))
      (node (ref "U6") (pin "1") (pinfunction "VSS_1") (pintype "passive"))
      (node (ref "U7") (pin "3") (pinfunction "VSS_3") (pintype "passive"))
      (node (ref "U8") (pin "23") (pinfunction "VSS_1_23") (pintype "passive"))
      (node (ref "U8") (pin "35") (pinfunction "VSS_2_35") (pintype "passive"))
      (node (ref "U8") (pin "47") (pinfunction "VSS_3_47") (pintype "passive"))
      (node (ref "U8") (pin "8") (pinfunction "VSSA_8") (pintype "passive"))
      (node (ref "U9") (pin "3") (pinfunction "VSS_3") (pintype "passive"))
      (node (ref "USB1") (pin "1") (pinfunction "GND_1") (pintype "passive"))
      (node (ref "USB1") (pin "12") (pinfunction "GND_12") (pintype "passive"))
      (node (ref "USB1") (pin "13") (pinfunction "SHELL_13") (pintype "passive"))
      (node (ref "USB1") (pin "14") (pinfunction "SHELL_14") (pintype "passive"))
    )
    (net (code "44") (name "Net-(D1-A)") (class "Default")
      (node (ref "D1") (pin "1") (pinfunction "A_1") (pintype "passive"))
      (node (ref "L1") (pin "2") (pinfunction "2_2") (pintype "passive"))
      (node (ref "U3") (pin "1") (pinfunction "LX_1") (pintype "passive"))
    )
    (net (code "45") (name "Net-(D2-Pad1)") (class "Default")
      (node (ref "D2") (pin "1") (pintype "passive"))
      (node (ref "R4") (pin "2") (pinfunction "2_2") (pintype "passive"))
    )
    (net (code "46") (name "Net-(D3-Pad1)") (class "Default")
      (node (ref "D3") (pin "1") (pintype "passive"))
      (node (ref "R6") (pin "2") (pinfunction "2_2") (pintype "passive"))
    )
    (net (code "47") (name "Net-(D4-K)") (class "Default")
      (node (ref "D4") (pin "2") (pinfunction "K_2") (pintype "passive"))
      (node (ref "Q1") (pin "2") (pinfunction "S_2") (pintype "passive"))
      (node (ref "SW1") (pin "2") (pinfunction "2_2") (pintype "passive"))
    )
    (net (code "48") (name "Net-(D5-Pad1)") (class "Default")
      (node (ref "D5") (pin "1") (pintype "passive"))
      (node (ref "R12") (pin "2") (pinfunction "2_2") (pintype "passive"))
    )
    (net (code "49") (name "Net-(D6-Pad1)") (class "Default")
      (node (ref "D6") (pin "1") (pintype "passive"))
      (node (ref "R14") (pin "2") (pinfunction "2_2") (pintype "passive"))
    )
    (net (code "50") (name "Net-(D7-Pad2)") (class "Default")
      (node (ref "D7") (pin "2") (pinfunction "2_2") (pintype "passive"))
      (node (ref "R21") (pin "1") (pinfunction "1_1") (pintype "passive"))
    )
    (net (code "51") (name "Net-(D7-Pad3)") (class "Default")
      (node (ref "D7") (pin "3") (pinfunction "3_3") (pintype "passive"))
      (node (ref "R24") (pin "2") (pinfunction "2_2") (pintype "passive"))
      (node (ref "R29") (pin "2") (pinfunction "2_2") (pintype "passive"))
    )
    (net (code "52") (name "Net-(D8-Pad2)") (class "Default")
      (node (ref "D8") (pin "2") (pinfunction "2_2") (pintype "passive"))
      (node (ref "R22") (pin "1") (pinfunction "1_1") (pintype "passive"))
    )
    (net (code "53") (name "Net-(D8-Pad3)") (class "Default")
      (node (ref "D8") (pin "3") (pinfunction "3_3") (pintype "passive"))
      (node (ref "R25") (pin "2") (pinfunction "2_2") (pintype "passive"))
      (node (ref "R30") (pin "2") (pinfunction "2_2") (pintype "passive"))
    )
    (net (code "54") (name "Net-(D9-Pad2)") (class "Default")
      (node (ref "D9") (pin "2") (pinfunction "2_2") (pintype "passive"))
      (node (ref "R23") (pin "1") (pinfunction "1_1") (pintype "passive"))
    )
    (net (code "55") (name "Net-(D9-Pad3)") (class "Default")
      (node (ref "D9") (pin "3") (pinfunction "3_3") (pintype "passive"))
      (node (ref "R26") (pin "2") (pinfunction "2_2") (pintype "passive"))
      (node (ref "R31") (pin "2") (pinfunction "2_2") (pintype "passive"))
    )
    (net (code "56") (name "Net-(D10-Pad2)") (class "Default")
      (node (ref "D10") (pin "2") (pinfunction "2_2") (pintype "passive"))
      (node (ref "R36") (pin "1") (pinfunction "1_1") (pintype "passive"))
    )
    (net (code "57") (name "Net-(D10-Pad3)") (class "Default")
      (node (ref "D10") (pin "3") (pinfunction "3_3") (pintype "passive"))
      (node (ref "R39") (pin "2") (pinfunction "2_2") (pintype "passive"))
      (node (ref "R42") (pin "2") (pinfunction "2_2") (pintype "passive"))
    )
    (net (code "58") (name "Net-(D11-Pad2)") (class "Default")
      (node (ref "D11") (pin "2") (pinfunction "2_2") (pintype "passive"))
      (node (ref "R37") (pin "1") (pinfunction "1_1") (pintype "passive"))
    )
    (net (code "59") (name "Net-(D11-Pad3)") (class "Default")
      (node (ref "D11") (pin "3") (pinfunction "3_3") (pintype "passive"))
      (node (ref "R40") (pin "2") (pinfunction "2_2") (pintype "passive"))
      (node (ref "R43") (pin "2") (pinfunction "2_2") (pintype "passive"))
    )
    (net (code "60") (name "Net-(LS1-B)") (class "Default")
      (node (ref "LS1") (pin "2") (pinfunction "B_2") (pintype "passive"))
      (node (ref "Q2") (pin "3") (pinfunction "C_3") (pintype "passive"))
    )
    (net (code "61") (name "Net-(Q2-B)") (class "Default")
      (node (ref "Q2") (pin "1") (pinfunction "B_1") (pintype "passive"))
      (node (ref "R20") (pin "2") (pinfunction "2_2") (pintype "passive"))
    )
    (net (code "62") (name "Net-(U2-RESET)") (class "Default")
      (node (ref "C7") (pin "1") (pinfunction "1_1") (pintype "passive"))
      (node (ref "R2") (pin "2") (pinfunction "2_2") (pintype "passive"))
      (node (ref "U2") (pin "23") (pinfunction "RESET_23") (pintype "passive"))
    )
    (net (code "63") (name "Net-(U3-FB)") (class "Default")
      (node (ref "R1") (pin "1") (pinfunction "1_1") (pintype "passive"))
      (node (ref "R3") (pin "2") (pinfunction "2_2") (pintype "passive"))
      (node (ref "U3") (pin "3") (pinfunction "FB_3") (pintype "passive"))
    )
    (net (code "64") (name "Net-(U3-OCP)") (class "Default")
      (node (ref "R5") (pin "2") (pinfunction "2_2") (pintype "passive"))
      (node (ref "U3") (pin "6") (pinfunction "OCP_6") (pintype "passive"))
    )
    (net (code "65") (name "Net-(U4-AD0)") (class "Default")
      (node (ref "R16") (pin "1") (pinfunction "1_1") (pintype "passive"))
      (node (ref "U4") (pin "9") (pinfunction "AD0_9") (pintype "passive"))
    )
    (net (code "66") (name "Net-(U4-CPOUT)") (class "Default")
      (node (ref "C14") (pin "1") (pinfunction "1_1") (pintype "passive"))
      (node (ref "U4") (pin "20") (pinfunction "CPOUT_20") (pintype "passive"))
    )
    (net (code "67") (name "Net-(U4-INT)") (class "Default")
      (node (ref "R17") (pin "2") (pinfunction "2_2") (pintype "passive"))
      (node (ref "U4") (pin "12") (pinfunction "INT_12") (pintype "passive"))
    )
    (net (code "68") (name "Net-(U4-REGOUT)") (class "Default")
      (node (ref "C15") (pin "1") (pinfunction "1_1") (pintype "passive"))
      (node (ref "U4") (pin "10") (pinfunction "REGOUT_10") (pintype "passive"))
    )
    (net (code "69") (name "Net-(U4-SCL)") (class "Default")
      (node (ref "R13") (pin "1") (pinfunction "1_1") (pintype "passive"))
      (node (ref "R9") (pin "2") (pinfunction "2_2") (pintype "passive"))
      (node (ref "U4") (pin "23") (pinfunction "SCL_23") (pintype "passive"))
    )
    (net (code "70") (name "Net-(U4-SDA)") (class "Default")
      (node (ref "R11") (pin "1") (pinfunction "1_1") (pintype "passive"))
      (node (ref "R8") (pin "2") (pinfunction "2_2") (pintype "passive"))
      (node (ref "U4") (pin "24") (pinfunction "SDA_24") (pintype "passive"))
    )
    (net (code "71") (name "Net-(U7-DOUT)") (class "Default")
      (node (ref "U7") (pin "2") (pinfunction "DOUT_2") (pintype "passive"))
      (node (ref "U9") (pin "4") (pinfunction "DIN_4") (pintype "passive"))
    )
    (net (code "72") (name "Net-(U8-VBAT)") (class "Default")
      (node (ref "R18") (pin "2") (pinfunction "2_2") (pintype "passive"))
      (node (ref "U8") (pin "1") (pinfunction "VBAT_1") (pintype "passive"))
    )
    (net (code "73") (name "VBAT") (class "Default")
      (node (ref "J1") (pin "2") (pinfunction "2_2") (pintype "passive"))
      (node (ref "Q1") (pin "3") (pinfunction "D_3") (pintype "passive"))
      (node (ref "R10") (pin "1") (pinfunction "1_1") (pintype "passive"))
    )
    (net (code "74") (name "VBUS") (class "Default")
      (node (ref "D4") (pin "1") (pinfunction "A_1") (pintype "passive"))
      (node (ref "Q1") (pin "1") (pinfunction "G_1") (pintype "passive"))
      (node (ref "R7") (pin "2") (pinfunction "2_2") (pintype "passive"))
      (node (ref "USB1") (pin "11") (pinfunction "VBUS_11") (pintype "passive"))
      (node (ref "USB1") (pin "2") (pinfunction "VBUS_2") (pintype "passive"))
    )
    (net (code "75") (name "VCC33") (class "Default")
      (node (ref "C12") (pin "1") (pinfunction "1_1") (pintype "passive"))
      (node (ref "C13") (pin "1") (pinfunction "1_1") (pintype "passive"))
      (node (ref "C21") (pin "1") (pinfunction "1_1") (pintype "passive"))
      (node (ref "C22") (pin "1") (pinfunction "1_1") (pintype "passive"))
      (node (ref "C23") (pin "1") (pinfunction "1_1") (pintype "passive"))
      (node (ref "C24") (pin "1") (pinfunction "1_1") (pintype "passive"))
      (node (ref "C25") (pin "1") (pinfunction "1_1") (pintype "passive"))
      (node (ref "R14") (pin "1") (pinfunction "1_1") (pintype "passive"))
      (node (ref "R18") (pin "1") (pinfunction "1_1") (pintype "passive"))
      (node (ref "U6") (pin "2") (pinfunction "VOUT_2") (pintype "passive"))
      (node (ref "U8") (pin "24") (pinfunction "VDD_1_24") (pintype "passive"))
      (node (ref "U8") (pin "36") (pinfunction "VDD_2_36") (pintype "passive"))
      (node (ref "U8") (pin "48") (pinfunction "VDD_3_48") (pintype "passive"))
      (node (ref "U8") (pin "9") (pinfunction "VDDA_9") (pintype "passive"))
    )
    (net (code "76") (name "unconnected-(SW1-Pad1)") (class "Default")
      (node (ref "SW1") (pin "1") (pinfunction "1_1") (pintype "passive"))
    )
    (net (code "77") (name "unconnected-(U1-RTS#-Pad4)") (class "Default")
      (node (ref "U1") (pin "4") (pinfunction "RTS#_4") (pintype "passive"))
    )
    (net (code "78") (name "unconnected-(U2-ALED-Pad17)") (class "Default")
      (node (ref "U2") (pin "17") (pinfunction "ALED_17") (pintype "passive"))
    )
    (net (code "79") (name "unconnected-(U2-EINT1-Pad21)") (class "Default")
      (node (ref "U2") (pin "21") (pinfunction "EINT1_21") (pintype "passive"))
    )
    (net (code "80") (name "unconnected-(U2-EINT2-Pad16)") (class "Default")
      (node (ref "U2") (pin "16") (pinfunction "EINT2_16") (pintype "passive"))
    )
    (net (code "81") (name "unconnected-(U2-INT3-Pad18)") (class "Default")
      (node (ref "U2") (pin "18") (pinfunction "INT3_18") (pintype "passive"))
    )
    (net (code "82") (name "unconnected-(U2-INT4-Pad15)") (class "Default")
      (node (ref "U2") (pin "15") (pinfunction "INT4_15") (pintype "passive"))
    )
    (net (code "83") (name "unconnected-(U2-INT5-Pad12)") (class "Default")
      (node (ref "U2") (pin "12") (pinfunction "INT5_12") (pintype "passive"))
    )
    (net (code "84") (name "unconnected-(U2-INT6-Pad11)") (class "Default")
      (node (ref "U2") (pin "11") (pinfunction "INT6_11") (pintype "passive"))
    )
    (net (code "85") (name "unconnected-(U2-INT7-Pad7)") (class "Default")
      (node (ref "U2") (pin "7") (pinfunction "INT7_7") (pintype "passive"))
    )
    (net (code "86") (name "unconnected-(U2-NULL-Pad2)") (class "Default")
      (node (ref "U2") (pin "2") (pinfunction "NULL_2") (pintype "passive"))
    )
    (net (code "87") (name "unconnected-(U2-NULL-Pad3)") (class "Default")
      (node (ref "U2") (pin "3") (pinfunction "NULL_3") (pintype "passive"))
    )
    (net (code "88") (name "unconnected-(U2-OUT1-Pad4)") (class "Default")
      (node (ref "U2") (pin "4") (pinfunction "OUT1_4") (pintype "passive"))
    )
    (net (code "89") (name "unconnected-(U2-OUT2-Pad5)") (class "Default")
      (node (ref "U2") (pin "5") (pinfunction "OUT2_5") (pintype "passive"))
    )
    (net (code "90") (name "unconnected-(U2-OUT3-Pad8)") (class "Default")
      (node (ref "U2") (pin "8") (pinfunction "OUT3_8") (pintype "passive"))
    )
    (net (code "91") (name "unconnected-(U2-OUT4-Pad9)") (class "Default")
      (node (ref "U2") (pin "9") (pinfunction "OUT4_9") (pintype "passive"))
    )
    (net (code "92") (name "unconnected-(U2-OUT4-Pad10)") (class "Default")
      (node (ref "U2") (pin "10") (pinfunction "OUT4_10") (pintype "passive"))
    )
    (net (code "93") (name "unconnected-(U2-OUT6-Pad13)") (class "Default")
      (node (ref "U2") (pin "13") (pinfunction "OUT6_13") (pintype "passive"))
    )
    (net (code "94") (name "unconnected-(U2-OUT7-Pad14)") (class "Default")
      (node (ref "U2") (pin "14") (pinfunction "OUT7_14") (pintype "passive"))
    )
    (net (code "95") (name "unconnected-(U2-PWRC-Pad22)") (class "Default")
      (node (ref "U2") (pin "22") (pinfunction "PWRC_22") (pintype "passive"))
    )
    (net (code "96") (name "unconnected-(U2-STAT-Pad6)") (class "Default")
      (node (ref "U2") (pin "6") (pinfunction "STAT_6") (pintype "passive"))
    )
    (net (code "97") (name "unconnected-(U4-AUX_CL-Pad7)") (class "Default")
      (node (ref "U4") (pin "7") (pinfunction "AUX_CL_7") (pintype "passive"))
    )
    (net (code "98") (name "unconnected-(U4-AUX_DA-Pad6)") (class "Default")
      (node (ref "U4") (pin "6") (pinfunction "AUX_DA_6") (pintype "passive"))
    )
    (net (code "99") (name "unconnected-(U4-CLKOUT-Pad22)") (class "Default")
      (node (ref "U4") (pin "22") (pinfunction "CLKOUT_22") (pintype "passive"))
    )
    (net (code "100") (name "unconnected-(U4-NC-Pad2)") (class "Default")
      (node (ref "U4") (pin "2") (pinfunction "NC_2") (pintype "passive"))
    )
    (net (code "101") (name "unconnected-(U4-NC-Pad3)") (class "Default")
      (node (ref "U4") (pin "3") (pinfunction "NC_3") (pintype "passive"))
    )
    (net (code "102") (name "unconnected-(U4-NC-Pad4)") (class "Default")
      (node (ref "U4") (pin "4") (pinfunction "NC_4") (pintype "passive"))
    )
    (net (code "103") (name "unconnected-(U4-NC-Pad5)") (class "Default")
      (node (ref "U4") (pin "5") (pinfunction "NC_5") (pintype "passive"))
    )
    (net (code "104") (name "unconnected-(U4-NC-Pad14)") (class "Default")
      (node (ref "U4") (pin "14") (pinfunction "NC_14") (pintype "passive"))
    )
    (net (code "105") (name "unconnected-(U4-NC-Pad15)") (class "Default")
      (node (ref "U4") (pin "15") (pinfunction "NC_15") (pintype "passive"))
    )
    (net (code "106") (name "unconnected-(U4-NC-Pad16)") (class "Default")
      (node (ref "U4") (pin "16") (pinfunction "NC_16") (pintype "passive"))
    )
    (net (code "107") (name "unconnected-(U4-NC-Pad17)") (class "Default")
      (node (ref "U4") (pin "17") (pinfunction "NC_17") (pintype "passive"))
    )
    (net (code "108") (name "unconnected-(U4-RESV-Pad19)") (class "Default")
      (node (ref "U4") (pin "19") (pinfunction "RESV_19") (pintype "passive"))
    )
    (net (code "109") (name "unconnected-(U4-RESV-Pad21)") (class "Default")
      (node (ref "U4") (pin "21") (pinfunction "RESV_21") (pintype "passive"))
    )
    (net (code "110") (name "unconnected-(U8-PB12{slash}SPI2_NSS{slash}I2C2_SMBAI{slash}USART3_CK{slash}TIM1_BKIN-Pad25)") (class "Default")
      (node (ref "U8") (pin "25") (pinfunction "PB12/SPI2_NSS/I2C2_SMBAI/USART3_CK/TIM1_BKIN_25") (pintype "passive"))
    )
    (net (code "111") (name "unconnected-(U8-PB13{slash}SPI2_SCK{slash}USART3_CTS{slash}TIM1_CH1N-Pad26)") (class "Default")
      (node (ref "U8") (pin "26") (pinfunction "PB13/SPI2_SCK/USART3_CTS/TIM1_CH1N_26") (pintype "passive"))
    )
    (net (code "112") (name "unconnected-(U9-DOUT-Pad2)") (class "Default")
      (node (ref "U9") (pin "2") (pinfunction "DOUT_2") (pintype "passive"))
    )
    (net (code "113") (name "unconnected-(USB1-CC1-Pad4)") (class "Default")
      (node (ref "USB1") (pin "4") (pinfunction "CC1_4") (pintype "passive"))
    )
    (net (code "114") (name "unconnected-(USB1-CC2-Pad10)") (class "Default")
      (node (ref "USB1") (pin "10") (pinfunction "CC2_10") (pintype "passive"))
    )
    (net (code "115") (name "unconnected-(USB1-SBU1-Pad9)") (class "Default")
      (node (ref "USB1") (pin "9") (pinfunction "SBU1_9") (pintype "passive"))
    )
    (net (code "116") (name "unconnected-(USB1-SBU2-Pad3)") (class "Default")
      (node (ref "USB1") (pin "3") (pinfunction "SBU2_3") (pintype "passive"))
    )
  )
)
